# 25.net
KiCad netlist of a schematic drawn in Altium Designer
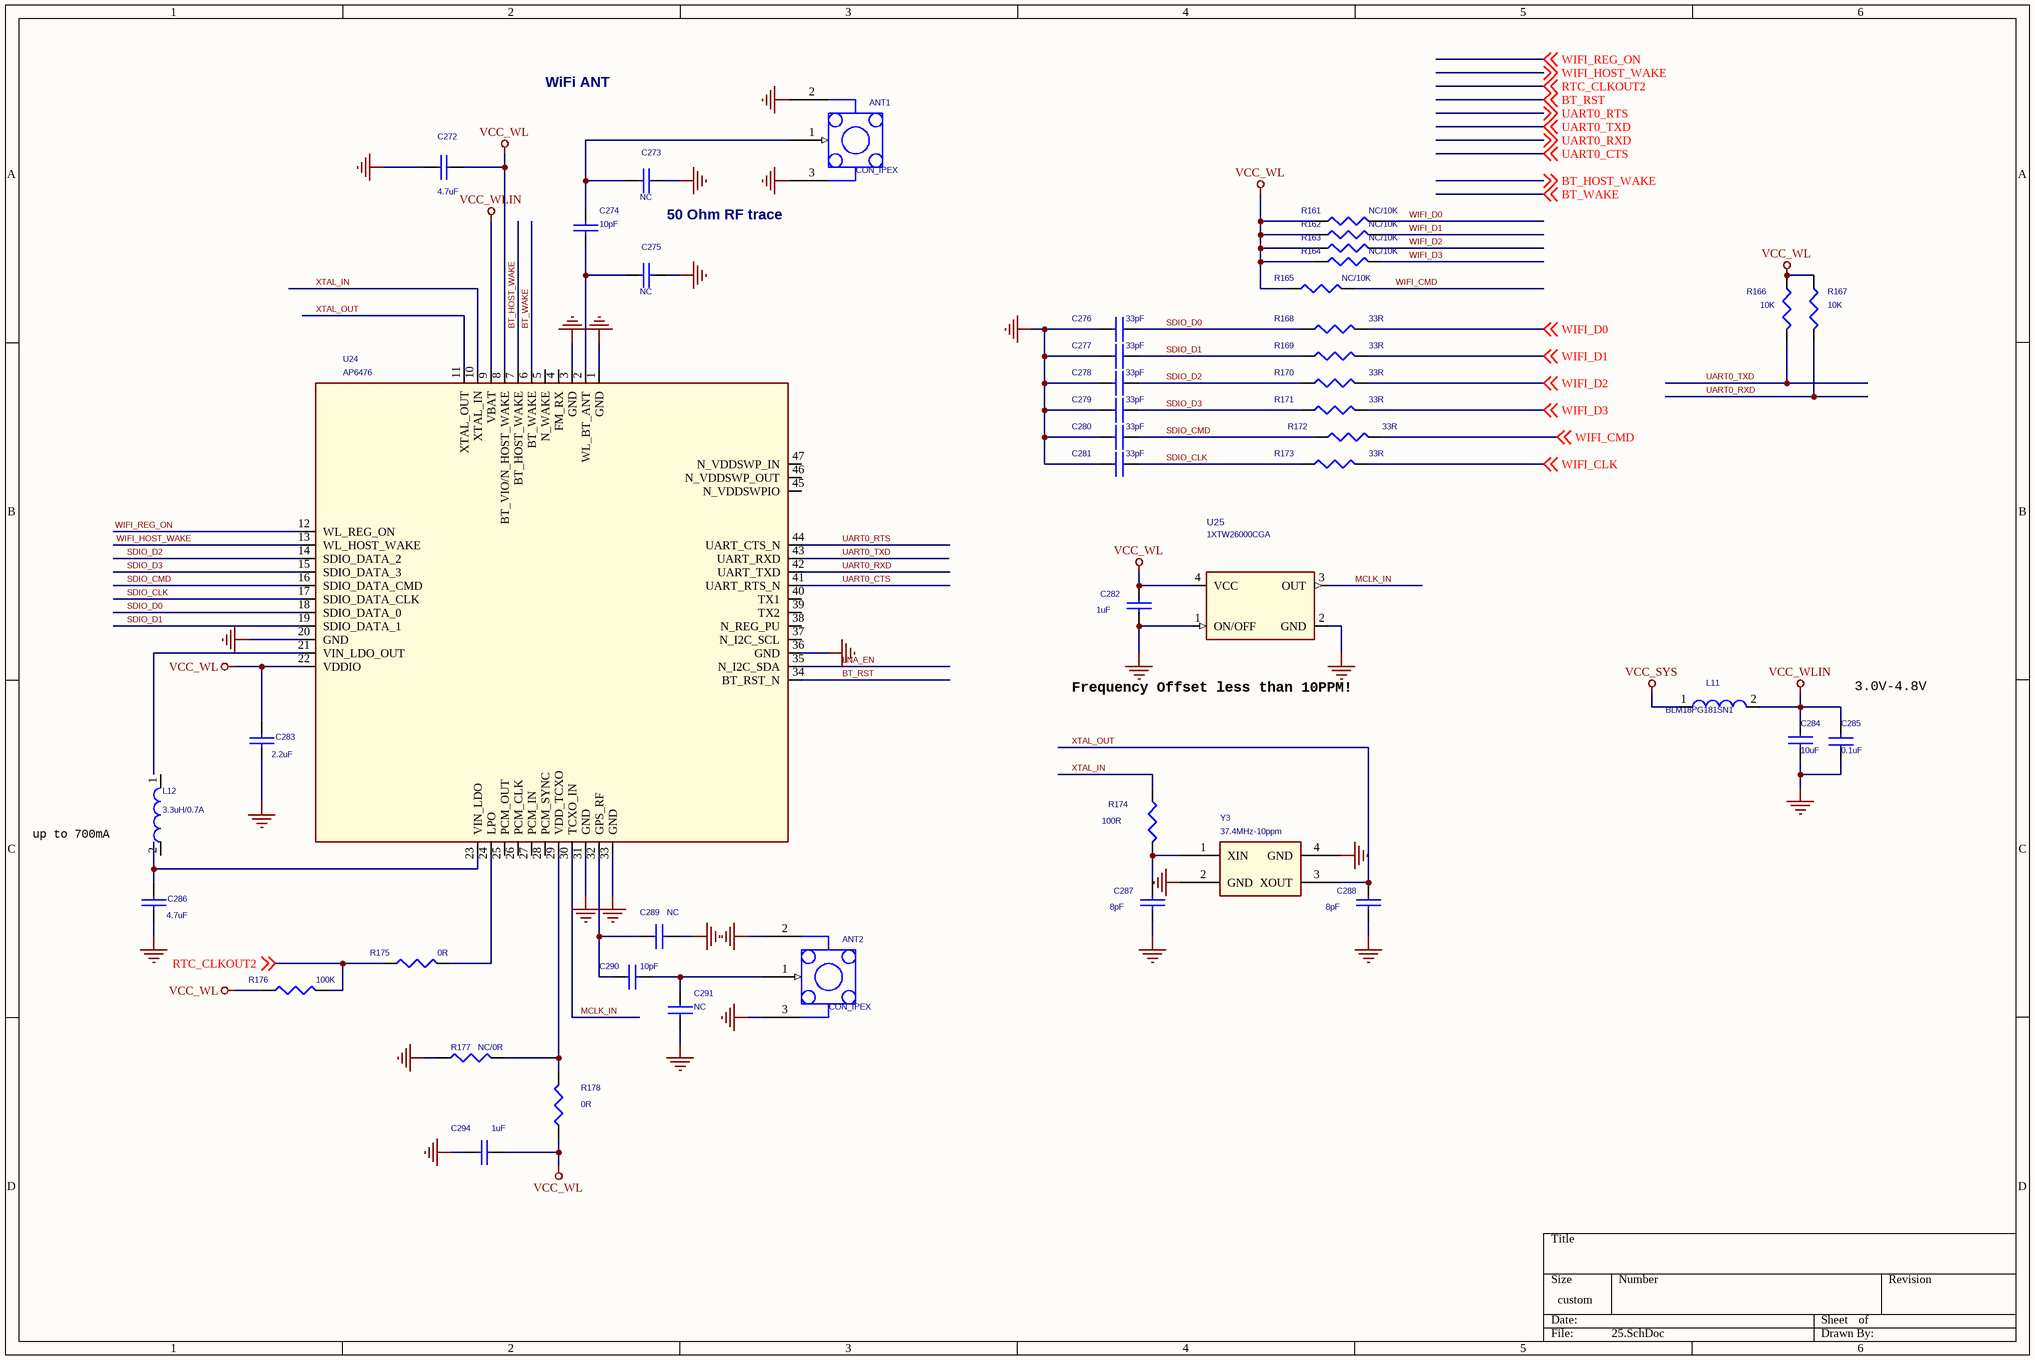
[diagram p0: 25.SchDoc]

(export (version "E")
  (design (tool "Eeschema 10.0.6"))
  (components
    (comp (ref "ANT1")
      (value "CON_IPEX")
      (footprint "ANT-JACKA-1")
      (description "Atanna jack,3pin,SMT")
      (libsource (lib "*") (part "CON_IPEX_0"))
    )
    (comp (ref "ANT2")
      (value "CON_IPEX")
      (footprint "ANT-JACKA-1")
      (description "Atanna jack,3pin,SMT")
      (libsource (lib "*") (part "CON_IPEX_0"))
    )
    (comp (ref "C272")
      (value "4.7uF")
      (footprint "C0603")
      (description "RoHS CHIP CAP 4.7uF +10/-10% X5R")
      (libsource (lib "*") (part "CAPNP_Dup1_1"))
    )
    (comp (ref "C273") (value "NC") (footprint "c0402") (libsource (lib "*") (part "CAPNP_Dup1_1")))
    (comp (ref "C274")
      (value "10pF")
      (footprint "c0402")
      (description "RoHS CHIP CAP 10pF +10/-10% X7R")
      (libsource (lib "*") (part "CAPNP_Dup1_1"))
    )
    (comp (ref "C275") (value "NC") (footprint "c0402") (libsource (lib "*") (part "CAPNP_Dup1_1")))
    (comp (ref "C276")
      (value "33pF")
      (footprint "c0402")
      (description "CAP,MLCC,10uF,+/-10%,X5R,6.3V,SMD0805")
      (libsource (lib "*") (part "CAP NP_Dup1"))
    )
    (comp (ref "C277")
      (value "33pF")
      (footprint "c0402")
      (description "CAP,MLCC,10uF,+/-10%,X5R,6.3V,SMD0805")
      (libsource (lib "*") (part "CAP NP_Dup1"))
    )
    (comp (ref "C278")
      (value "33pF")
      (footprint "c0402")
      (description "CAP,MLCC,10uF,+/-10%,X5R,6.3V,SMD0805")
      (libsource (lib "*") (part "CAP NP_Dup1"))
    )
    (comp (ref "C279")
      (value "33pF")
      (footprint "c0402")
      (description "CAP,MLCC,10uF,+/-10%,X5R,6.3V,SMD0805")
      (libsource (lib "*") (part "CAP NP_Dup1"))
    )
    (comp (ref "C280")
      (value "33pF")
      (footprint "c0402")
      (description "CAP,MLCC,10uF,+/-10%,X5R,6.3V,SMD0805")
      (libsource (lib "*") (part "CAP NP_Dup1"))
    )
    (comp (ref "C281")
      (value "33pF")
      (footprint "c0402")
      (description "CAP,MLCC,10uF,+/-10%,X5R,6.3V,SMD0805")
      (libsource (lib "*") (part "CAP NP_Dup1"))
    )
    (comp (ref "C282")
      (value "1uF")
      (footprint "c0402")
      (description "RoHS CHIP CAP 8pF +/-1% NPO")
      (libsource (lib "*") (part "CAPNP_Dup1_1"))
    )
    (comp (ref "C283")
      (value "2.2uF")
      (footprint "C0402")
      (description "RoHS CHIP CAP 2.2uF +10/-10% X5R")
      (libsource (lib "*") (part "CAPNP_Dup1_1"))
    )
    (comp (ref "C284")
      (value "10uF")
      (footprint "C0402")
      (description "CAP,MLCC,4.7uF,+/-10%,X5R,6.3V,SMD0603")
      (libsource (lib "*") (part "CAP NP_Dup2"))
    )
    (comp (ref "C285")
      (value "0.1uF")
      (footprint "C0402")
      (description "CAP,MLCC,100nF,+/-10%,X7R,6.3V,SMD0402")
      (libsource (lib "*") (part "CAP NP_Dup2"))
    )
    (comp (ref "C286")
      (value "4.7uF")
      (footprint "C0603")
      (description "RoHS CHIP CAP 4.7uF +10/-10% X5R")
      (libsource (lib "*") (part "CAPNP_Dup1_1"))
    )
    (comp (ref "C287")
      (value "8pF")
      (footprint "c0402")
      (description "RoHS CHIP CAP 8pF +/-1% NPO")
      (libsource (lib "*") (part "CAPNP_Dup1_1"))
    )
    (comp (ref "C288")
      (value "8pF")
      (footprint "c0402")
      (description "RoHS CHIP CAP 8pF +/-1% NPO")
      (libsource (lib "*") (part "CAPNP_Dup1_1"))
    )
    (comp (ref "C289")
      (value "NC")
      (footprint "C0402")
      (description "RoHS CHIP CAP 2.2uF +10/-10% X5R")
      (libsource (lib "*") (part "CAP NP_Dup2"))
    )
    (comp (ref "C290")
      (value "10pF")
      (footprint "C0402")
      (description "RoHS CHIP CAP 2.2uF +10/-10% X5R")
      (libsource (lib "*") (part "CAP NP_Dup2"))
    )
    (comp (ref "C291")
      (value "NC")
      (footprint "C0402")
      (description "RoHS CHIP CAP 2.2uF +10/-10% X5R")
      (libsource (lib "*") (part "CAP NP_Dup2"))
    )
    (comp (ref "C294")
      (value "1uF")
      (footprint "c0402")
      (description "RoHS CHIP CAP 8pF +/-1% NPO")
      (libsource (lib "*") (part "CAPNP_Dup1_1"))
    )
    (comp (ref "L11")
      (value "BLM18PG181SN1")
      (footprint "L0603")
      (fields (field (name "PART NUMBER") "SM01V00480I"))
      (libsource (lib "*") (part "INDUCTOR"))
    )
    (comp (ref "L12")
      (value "3.3uH/0.7A")
      (footprint "IND-3X3")
      (description "CoilInd,Shielded(SHLD),1.5uH@100KHz,+/-30%,0.7A,40mOhm,SMD,3.0*3.0*2.0")
      (libsource (lib "") (part "INDUCTOR_1"))
    )
    (comp (ref "R161")
      (value "NC/10K")
      (footprint "R0402")
      (description "ROHS CHIP RES 10K 1/16W +/-5%")
      (libsource (lib "*") (part "RESISTOR_Dup1"))
    )
    (comp (ref "R162")
      (value "NC/10K")
      (footprint "R0402")
      (description "ROHS CHIP RES 10K 1/16W +/-5%")
      (libsource (lib "*") (part "RESISTOR_Dup1"))
    )
    (comp (ref "R163")
      (value "NC/10K")
      (footprint "R0402")
      (description "ROHS CHIP RES 10K 1/16W +/-5%")
      (libsource (lib "*") (part "RESISTOR_Dup1"))
    )
    (comp (ref "R164")
      (value "NC/10K")
      (footprint "R0402")
      (description "ROHS CHIP RES 10K 1/16W +/-5%")
      (libsource (lib "*") (part "RESISTOR_Dup1"))
    )
    (comp (ref "R165")
      (value "NC/10K")
      (footprint "R0402")
      (description "ROHS CHIP RES 10K 1/16W +/-5%")
      (libsource (lib "*") (part "RESISTOR_Dup1"))
    )
    (comp (ref "R166")
      (value "10K")
      (footprint "r0402")
      (description "ROHS CHIP RES 10K 1/16W +/-5%")
      (libsource (lib "*") (part "RESISTOR_4"))
    )
    (comp (ref "R167")
      (value "10K")
      (footprint "r0402")
      (description "ROHS CHIP RES 10K 1/16W +/-5%")
      (libsource (lib "*") (part "RESISTOR_4"))
    )
    (comp (ref "R168")
      (value "33R")
      (footprint "R0402")
      (description "RES,thick film,33Ohm,+/-5%,1/16W,SMD0402")
      (libsource (lib "*") (part "RESISTOR_Dup1"))
    )
    (comp (ref "R169")
      (value "33R")
      (footprint "R0402")
      (description "RES,thick film,33Ohm,+/-5%,1/16W,SMD0402")
      (libsource (lib "*") (part "RESISTOR_Dup1"))
    )
    (comp (ref "R170")
      (value "33R")
      (footprint "R0402")
      (description "RES,thick film,33Ohm,+/-5%,1/16W,SMD0402")
      (libsource (lib "*") (part "RESISTOR_Dup1"))
    )
    (comp (ref "R171")
      (value "33R")
      (footprint "R0402")
      (description "RES,thick film,33Ohm,+/-5%,1/16W,SMD0402")
      (libsource (lib "*") (part "RESISTOR_Dup1"))
    )
    (comp (ref "R172")
      (value "33R")
      (footprint "R0402")
      (description "RES,thick film,33Ohm,+/-5%,1/16W,SMD0402")
      (libsource (lib "*") (part "RESISTOR_Dup1"))
    )
    (comp (ref "R173")
      (value "33R")
      (footprint "R0402")
      (description "RES,thick film,33Ohm,+/-5%,1/16W,SMD0402")
      (libsource (lib "*") (part "RESISTOR_Dup1"))
    )
    (comp (ref "R174")
      (value "100R")
      (footprint "R0402")
      (description "ROHS CHIP RES 100 Ohm 1/16W +/-5%")
      (libsource (lib "*") (part "R_0"))
    )
    (comp (ref "R175")
      (value "0R")
      (footprint "R0402")
      (description "ROHS CHIP RES 200 Ohm 1/16W +/-5%")
      (libsource (lib "*") (part "RESISTOR_Dup1"))
    )
    (comp (ref "R176")
      (value "100K")
      (footprint "R0402")
      (description "ROHS CHIP RES 100K 1/16W +/-5%")
      (libsource (lib "*") (part "RESISTOR_Dup1"))
    )
    (comp (ref "R177")
      (value "NC/0R")
      (footprint "R0402")
      (description "RES,thick film,33Ohm,+/-5%,1/16W,SMD0402")
      (libsource (lib "*") (part "RESISTOR_Dup1"))
    )
    (comp (ref "R178")
      (value "0R")
      (footprint "R0402")
      (description "RES,thick film,33Ohm,+/-5%,1/16W,SMD0402")
      (libsource (lib "*") (part "RESISTOR_Dup1"))
    )
    (comp (ref "U24")
      (value "AP6476")
      (footprint "AP6XXX")
      (description "WIFI&BT")
      (libsource (lib "*") (part "AP6493_0"))
    )
    (comp (ref "U25")
      (value "1XTW26000CGA")
      (footprint "CRY-D3225")
      (description "1XTW26000CGA  KDS TCXO 26MHZ 1.8V 0.5PPM ,SMD3225")
      (libsource (lib "*") (part "CRYSTAL OSC"))
    )
    (comp (ref "Y3")
      (value "37.4MHz-10ppm")
      (footprint "CRY-3225")
      (description "Crystal,24.000MHz,+/-20ppm,12pF,SMD3225,-10°C ~ +60   °C")
      (libsource (lib "*") (part "CRYSTAL-4_0"))
    )
  )
  (nets
    (net (code "1") (name "/LNA_EN") (class "Default")
      (node (ref "U24") (pin "35") (pinfunction "N_I2C_SDA_35") (pintype "passive"))
    )
    (net (code "2") (name "/MCLK_IN") (class "Default")
      (node (ref "U24") (pin "30") (pinfunction "TCXO_IN_30") (pintype "passive"))
      (node (ref "U25") (pin "3") (pinfunction "OUT_3") (pintype "output"))
    )
    (net (code "3") (name "/SDIO_CLK") (class "Default")
      (node (ref "C281") (pin "1") (pinfunction "1_1") (pintype "passive"))
      (node (ref "R173") (pin "1") (pinfunction "1_1") (pintype "passive"))
      (node (ref "U24") (pin "17") (pinfunction "SDIO_DATA_CLK_17") (pintype "passive"))
    )
    (net (code "4") (name "/SDIO_CMD") (class "Default")
      (node (ref "C280") (pin "1") (pinfunction "1_1") (pintype "passive"))
      (node (ref "R172") (pin "1") (pinfunction "1_1") (pintype "passive"))
      (node (ref "U24") (pin "16") (pinfunction "SDIO_DATA_CMD_16") (pintype "passive"))
    )
    (net (code "5") (name "/SDIO_D0") (class "Default")
      (node (ref "C276") (pin "1") (pinfunction "1_1") (pintype "passive"))
      (node (ref "R168") (pin "1") (pinfunction "1_1") (pintype "passive"))
      (node (ref "U24") (pin "18") (pinfunction "SDIO_DATA_0_18") (pintype "passive"))
    )
    (net (code "6") (name "/SDIO_D1") (class "Default")
      (node (ref "C277") (pin "1") (pinfunction "1_1") (pintype "passive"))
      (node (ref "R169") (pin "1") (pinfunction "1_1") (pintype "passive"))
      (node (ref "U24") (pin "19") (pinfunction "SDIO_DATA_1_19") (pintype "passive"))
    )
    (net (code "7") (name "/SDIO_D2") (class "Default")
      (node (ref "C278") (pin "1") (pinfunction "1_1") (pintype "passive"))
      (node (ref "R170") (pin "1") (pinfunction "1_1") (pintype "passive"))
      (node (ref "U24") (pin "14") (pinfunction "SDIO_DATA_2_14") (pintype "passive"))
    )
    (net (code "8") (name "/SDIO_D3") (class "Default")
      (node (ref "C279") (pin "1") (pinfunction "1_1") (pintype "passive"))
      (node (ref "R171") (pin "1") (pinfunction "1_1") (pintype "passive"))
      (node (ref "U24") (pin "15") (pinfunction "SDIO_DATA_3_15") (pintype "passive"))
    )
    (net (code "9") (name "/XTAL_IN") (class "Default")
      (node (ref "R174") (pin "2") (pinfunction "2_2") (pintype "passive"))
      (node (ref "U24") (pin "10") (pinfunction "XTAL_IN_10") (pintype "passive"))
    )
    (net (code "10") (name "/XTAL_OUT") (class "Default")
      (node (ref "C288") (pin "2") (pinfunction "2_2") (pintype "passive"))
      (node (ref "U24") (pin "11") (pinfunction "XTAL_OUT_11") (pintype "passive"))
      (node (ref "Y3") (pin "3") (pinfunction "XOUT_3") (pintype "passive"))
    )
    (net (code "11") (name "BT_HOST_WAKE") (class "Default")
      (node (ref "U24") (pin "7") (pinfunction "BT_HOST_WAKE_7") (pintype "passive"))
    )
    (net (code "12") (name "BT_RST") (class "Default")
      (node (ref "U24") (pin "34") (pinfunction "BT_RST_N_34") (pintype "passive"))
    )
    (net (code "13") (name "BT_WAKE") (class "Default")
      (node (ref "U24") (pin "6") (pinfunction "BT_WAKE_6") (pintype "passive"))
    )
    (net (code "14") (name "GND") (class "Default")
      (node (ref "ANT1") (pin "2") (pinfunction "GND1_2") (pintype "power_in"))
      (node (ref "ANT1") (pin "3") (pinfunction "GND2_3") (pintype "power_in"))
      (node (ref "ANT2") (pin "2") (pinfunction "GND1_2") (pintype "power_in"))
      (node (ref "ANT2") (pin "3") (pinfunction "GND2_3") (pintype "power_in"))
      (node (ref "C272") (pin "2") (pinfunction "2_2") (pintype "passive"))
      (node (ref "C273") (pin "2") (pinfunction "2_2") (pintype "passive"))
      (node (ref "C275") (pin "2") (pinfunction "2_2") (pintype "passive"))
      (node (ref "C276") (pin "2") (pinfunction "2_2") (pintype "passive"))
      (node (ref "C277") (pin "2") (pinfunction "2_2") (pintype "passive"))
      (node (ref "C278") (pin "2") (pinfunction "2_2") (pintype "passive"))
      (node (ref "C279") (pin "2") (pinfunction "2_2") (pintype "passive"))
      (node (ref "C280") (pin "2") (pinfunction "2_2") (pintype "passive"))
      (node (ref "C281") (pin "2") (pinfunction "2_2") (pintype "passive"))
      (node (ref "C282") (pin "1") (pinfunction "1_1") (pintype "passive"))
      (node (ref "C283") (pin "1") (pinfunction "1_1") (pintype "passive"))
      (node (ref "C284") (pin "2") (pinfunction "2_2") (pintype "passive"))
      (node (ref "C285") (pin "1") (pinfunction "1_1") (pintype "passive"))
      (node (ref "C286") (pin "1") (pinfunction "1_1") (pintype "passive"))
      (node (ref "C287") (pin "1") (pinfunction "1_1") (pintype "passive"))
      (node (ref "C288") (pin "1") (pinfunction "1_1") (pintype "passive"))
      (node (ref "C289") (pin "2") (pinfunction "2_2") (pintype "passive"))
      (node (ref "C291") (pin "2") (pinfunction "2_2") (pintype "passive"))
      (node (ref "C294") (pin "2") (pinfunction "2_2") (pintype "passive"))
      (node (ref "R177") (pin "2") (pinfunction "2_2") (pintype "passive"))
      (node (ref "U24") (pin "1") (pinfunction "GND_1") (pintype "power_in"))
      (node (ref "U24") (pin "20") (pinfunction "GND_20") (pintype "power_in"))
      (node (ref "U24") (pin "3") (pinfunction "GND_3") (pintype "power_in"))
      (node (ref "U24") (pin "31") (pinfunction "GND_31") (pintype "power_in"))
      (node (ref "U24") (pin "33") (pinfunction "GND_33") (pintype "power_in"))
      (node (ref "U24") (pin "36") (pinfunction "GND_36") (pintype "power_in"))
      (node (ref "U25") (pin "1") (pinfunction "ON/OFF_1") (pintype "input"))
      (node (ref "U25") (pin "2") (pinfunction "GND_2") (pintype "power_in"))
      (node (ref "Y3") (pin "2") (pinfunction "GND_2") (pintype "power_in"))
      (node (ref "Y3") (pin "4") (pinfunction "GND_4") (pintype "power_in"))
    )
    (net (code "15") (name "Net-(ANT1-IN)") (class "Default")
      (node (ref "ANT1") (pin "1") (pinfunction "IN_1") (pintype "input"))
      (node (ref "C273") (pin "1") (pinfunction "1_1") (pintype "passive"))
      (node (ref "C274") (pin "2") (pinfunction "2_2") (pintype "passive"))
    )
    (net (code "16") (name "Net-(ANT2-IN)") (class "Default")
      (node (ref "ANT2") (pin "1") (pinfunction "IN_1") (pintype "input"))
      (node (ref "C290") (pin "2") (pinfunction "2_2") (pintype "passive"))
      (node (ref "C291") (pin "1") (pinfunction "1_1") (pintype "passive"))
    )
    (net (code "17") (name "Net-(U24-GPS_RF)") (class "Default")
      (node (ref "C289") (pin "1") (pinfunction "1_1") (pintype "passive"))
      (node (ref "C290") (pin "1") (pinfunction "1_1") (pintype "passive"))
      (node (ref "U24") (pin "32") (pinfunction "GPS_RF_32") (pintype "passive"))
    )
    (net (code "18") (name "Net-(U24-LPO)") (class "Default")
      (node (ref "R175") (pin "2") (pinfunction "2_2") (pintype "passive"))
      (node (ref "U24") (pin "24") (pinfunction "LPO_24") (pintype "passive"))
    )
    (net (code "19") (name "Net-(U24-VDD_TCXO)") (class "Default")
      (node (ref "R177") (pin "1") (pinfunction "1_1") (pintype "passive"))
      (node (ref "R178") (pin "1") (pinfunction "1_1") (pintype "passive"))
      (node (ref "U24") (pin "29") (pinfunction "VDD_TCXO_29") (pintype "passive"))
    )
    (net (code "20") (name "Net-(U24-VIN_LDO)") (class "Default")
      (node (ref "C286") (pin "2") (pinfunction "2_2") (pintype "passive"))
      (node (ref "U24") (pin "23") (pinfunction "VIN_LDO_23") (pintype "passive"))
    )
    (net (code "21") (name "Net-(U24-WL_BT_ANT)") (class "Default")
      (node (ref "C274") (pin "1") (pinfunction "1_1") (pintype "passive"))
      (node (ref "C275") (pin "1") (pinfunction "1_1") (pintype "passive"))
      (node (ref "U24") (pin "2") (pinfunction "WL_BT_ANT_2") (pintype "passive"))
    )
    (net (code "22") (name "Net-(Y3-XIN)") (class "Default")
      (node (ref "C287") (pin "2") (pinfunction "2_2") (pintype "passive"))
      (node (ref "R174") (pin "1") (pinfunction "1_1") (pintype "passive"))
      (node (ref "Y3") (pin "1") (pinfunction "XIN_1") (pintype "passive"))
    )
    (net (code "23") (name "RTC_CLKOUT2") (class "Default")
      (node (ref "R175") (pin "1") (pinfunction "1_1") (pintype "passive"))
      (node (ref "R176") (pin "2") (pinfunction "2_2") (pintype "passive"))
    )
    (net (code "24") (name "UART0_CTS") (class "Default")
      (node (ref "U24") (pin "41") (pinfunction "UART_RTS_N_41") (pintype "passive"))
    )
    (net (code "25") (name "UART0_RTS") (class "Default")
      (node (ref "U24") (pin "44") (pinfunction "UART_CTS_N_44") (pintype "passive"))
    )
    (net (code "26") (name "UART0_RXD") (class "Default")
      (node (ref "R167") (pin "1") (pinfunction "1_1") (pintype "passive"))
      (node (ref "U24") (pin "42") (pinfunction "UART_TXD_42") (pintype "passive"))
    )
    (net (code "27") (name "UART0_TXD") (class "Default")
      (node (ref "R166") (pin "1") (pinfunction "1_1") (pintype "passive"))
      (node (ref "U24") (pin "43") (pinfunction "UART_RXD_43") (pintype "passive"))
    )
    (net (code "28") (name "VCC_SYS") (class "Default")
      (node (ref "L11") (pin "1") (pinfunction "1_1") (pintype "passive"))
    )
    (net (code "29") (name "VCC_WL") (class "Default")
      (node (ref "C272") (pin "1") (pinfunction "1_1") (pintype "passive"))
      (node (ref "C282") (pin "2") (pinfunction "2_2") (pintype "passive"))
      (node (ref "C283") (pin "2") (pinfunction "2_2") (pintype "passive"))
      (node (ref "C294") (pin "1") (pinfunction "1_1") (pintype "passive"))
      (node (ref "R161") (pin "1") (pinfunction "1_1") (pintype "passive"))
      (node (ref "R162") (pin "1") (pinfunction "1_1") (pintype "passive"))
      (node (ref "R163") (pin "1") (pinfunction "1_1") (pintype "passive"))
      (node (ref "R164") (pin "1") (pinfunction "1_1") (pintype "passive"))
      (node (ref "R165") (pin "1") (pinfunction "1_1") (pintype "passive"))
      (node (ref "R166") (pin "2") (pinfunction "2_2") (pintype "passive"))
      (node (ref "R167") (pin "2") (pinfunction "2_2") (pintype "passive"))
      (node (ref "R176") (pin "1") (pinfunction "1_1") (pintype "passive"))
      (node (ref "R178") (pin "2") (pinfunction "2_2") (pintype "passive"))
      (node (ref "U24") (pin "22") (pinfunction "VDDIO_22") (pintype "passive"))
      (node (ref "U24") (pin "8") (pinfunction "BT_VIO/N_HOST_WAKE_8") (pintype "passive"))
      (node (ref "U25") (pin "4") (pinfunction "VCC_4") (pintype "power_in"))
    )
    (net (code "30") (name "VCC_WLIN") (class "Default")
      (node (ref "C284") (pin "1") (pinfunction "1_1") (pintype "passive"))
      (node (ref "C285") (pin "2") (pinfunction "2_2") (pintype "passive"))
      (node (ref "L11") (pin "2") (pinfunction "2_2") (pintype "passive"))
      (node (ref "U24") (pin "9") (pinfunction "VBAT_9") (pintype "passive"))
    )
    (net (code "31") (name "WIFI_CLK") (class "Default")
      (node (ref "R173") (pin "2") (pinfunction "2_2") (pintype "passive"))
    )
    (net (code "32") (name "WIFI_CMD") (class "Default")
      (node (ref "R165") (pin "2") (pinfunction "2_2") (pintype "passive"))
      (node (ref "R172") (pin "2") (pinfunction "2_2") (pintype "passive"))
    )
    (net (code "33") (name "WIFI_D0") (class "Default")
      (node (ref "R161") (pin "2") (pinfunction "2_2") (pintype "passive"))
      (node (ref "R168") (pin "2") (pinfunction "2_2") (pintype "passive"))
    )
    (net (code "34") (name "WIFI_D1") (class "Default")
      (node (ref "R162") (pin "2") (pinfunction "2_2") (pintype "passive"))
      (node (ref "R169") (pin "2") (pinfunction "2_2") (pintype "passive"))
    )
    (net (code "35") (name "WIFI_D2") (class "Default")
      (node (ref "R163") (pin "2") (pinfunction "2_2") (pintype "passive"))
      (node (ref "R170") (pin "2") (pinfunction "2_2") (pintype "passive"))
    )
    (net (code "36") (name "WIFI_D3") (class "Default")
      (node (ref "R164") (pin "2") (pinfunction "2_2") (pintype "passive"))
      (node (ref "R171") (pin "2") (pinfunction "2_2") (pintype "passive"))
    )
    (net (code "37") (name "WIFI_HOST_WAKE") (class "Default")
      (node (ref "U24") (pin "13") (pinfunction "WL_HOST_WAKE_13") (pintype "passive"))
    )
    (net (code "38") (name "WIFI_REG_ON") (class "Default")
      (node (ref "U24") (pin "12") (pinfunction "WL_REG_ON_12") (pintype "passive"))
    )
    (net (code "39") (name "unconnected-(L12-Pad1)") (class "Default")
      (node (ref "L12") (pin "1") (pinfunction "1_1") (pintype "passive"))
    )
    (net (code "40") (name "unconnected-(L12-Pad2)") (class "Default")
      (node (ref "L12") (pin "2") (pinfunction "2_2") (pintype "passive"))
    )
    (net (code "41") (name "unconnected-(U24-FM_RX-Pad4)") (class "Default")
      (node (ref "U24") (pin "4") (pinfunction "FM_RX_4") (pintype "passive"))
    )
    (net (code "42") (name "unconnected-(U24-N_I2C_SCL-Pad37)") (class "Default")
      (node (ref "U24") (pin "37") (pinfunction "N_I2C_SCL_37") (pintype "passive"))
    )
    (net (code "43") (name "unconnected-(U24-N_REG_PU-Pad38)") (class "Default")
      (node (ref "U24") (pin "38") (pinfunction "N_REG_PU_38") (pintype "passive"))
    )
    (net (code "44") (name "unconnected-(U24-N_VDDSWPIO-Pad45)") (class "Default")
      (node (ref "U24") (pin "45") (pinfunction "N_VDDSWPIO_45") (pintype "passive"))
    )
    (net (code "45") (name "unconnected-(U24-N_VDDSWP_IN-Pad47)") (class "Default")
      (node (ref "U24") (pin "47") (pinfunction "N_VDDSWP_IN_47") (pintype "passive"))
    )
    (net (code "46") (name "unconnected-(U24-N_VDDSWP_OUT-Pad46)") (class "Default")
      (node (ref "U24") (pin "46") (pinfunction "N_VDDSWP_OUT_46") (pintype "passive"))
    )
    (net (code "47") (name "unconnected-(U24-N_WAKE-Pad5)") (class "Default")
      (node (ref "U24") (pin "5") (pinfunction "N_WAKE_5") (pintype "passive"))
    )
    (net (code "48") (name "unconnected-(U24-PCM_CLK-Pad26)") (class "Default")
      (node (ref "U24") (pin "26") (pinfunction "PCM_CLK_26") (pintype "passive"))
    )
    (net (code "49") (name "unconnected-(U24-PCM_IN-Pad27)") (class "Default")
      (node (ref "U24") (pin "27") (pinfunction "PCM_IN_27") (pintype "passive"))
    )
    (net (code "50") (name "unconnected-(U24-PCM_OUT-Pad25)") (class "Default")
      (node (ref "U24") (pin "25") (pinfunction "PCM_OUT_25") (pintype "passive"))
    )
    (net (code "51") (name "unconnected-(U24-PCM_SYNC-Pad28)") (class "Default")
      (node (ref "U24") (pin "28") (pinfunction "PCM_SYNC_28") (pintype "passive"))
    )
    (net (code "52") (name "unconnected-(U24-TX1-Pad40)") (class "Default")
      (node (ref "U24") (pin "40") (pinfunction "TX1_40") (pintype "passive"))
    )
    (net (code "53") (name "unconnected-(U24-TX2-Pad39)") (class "Default")
      (node (ref "U24") (pin "39") (pinfunction "TX2_39") (pintype "passive"))
    )
    (net (code "54") (name "unconnected-(U24-VIN_LDO_OUT-Pad21)") (class "Default")
      (node (ref "U24") (pin "21") (pinfunction "VIN_LDO_OUT_21") (pintype "passive"))
    )
  )
)
